# VESC_POWER_75100_SCH.net
KiCad netlist of a schematic drawn in Altium Designer
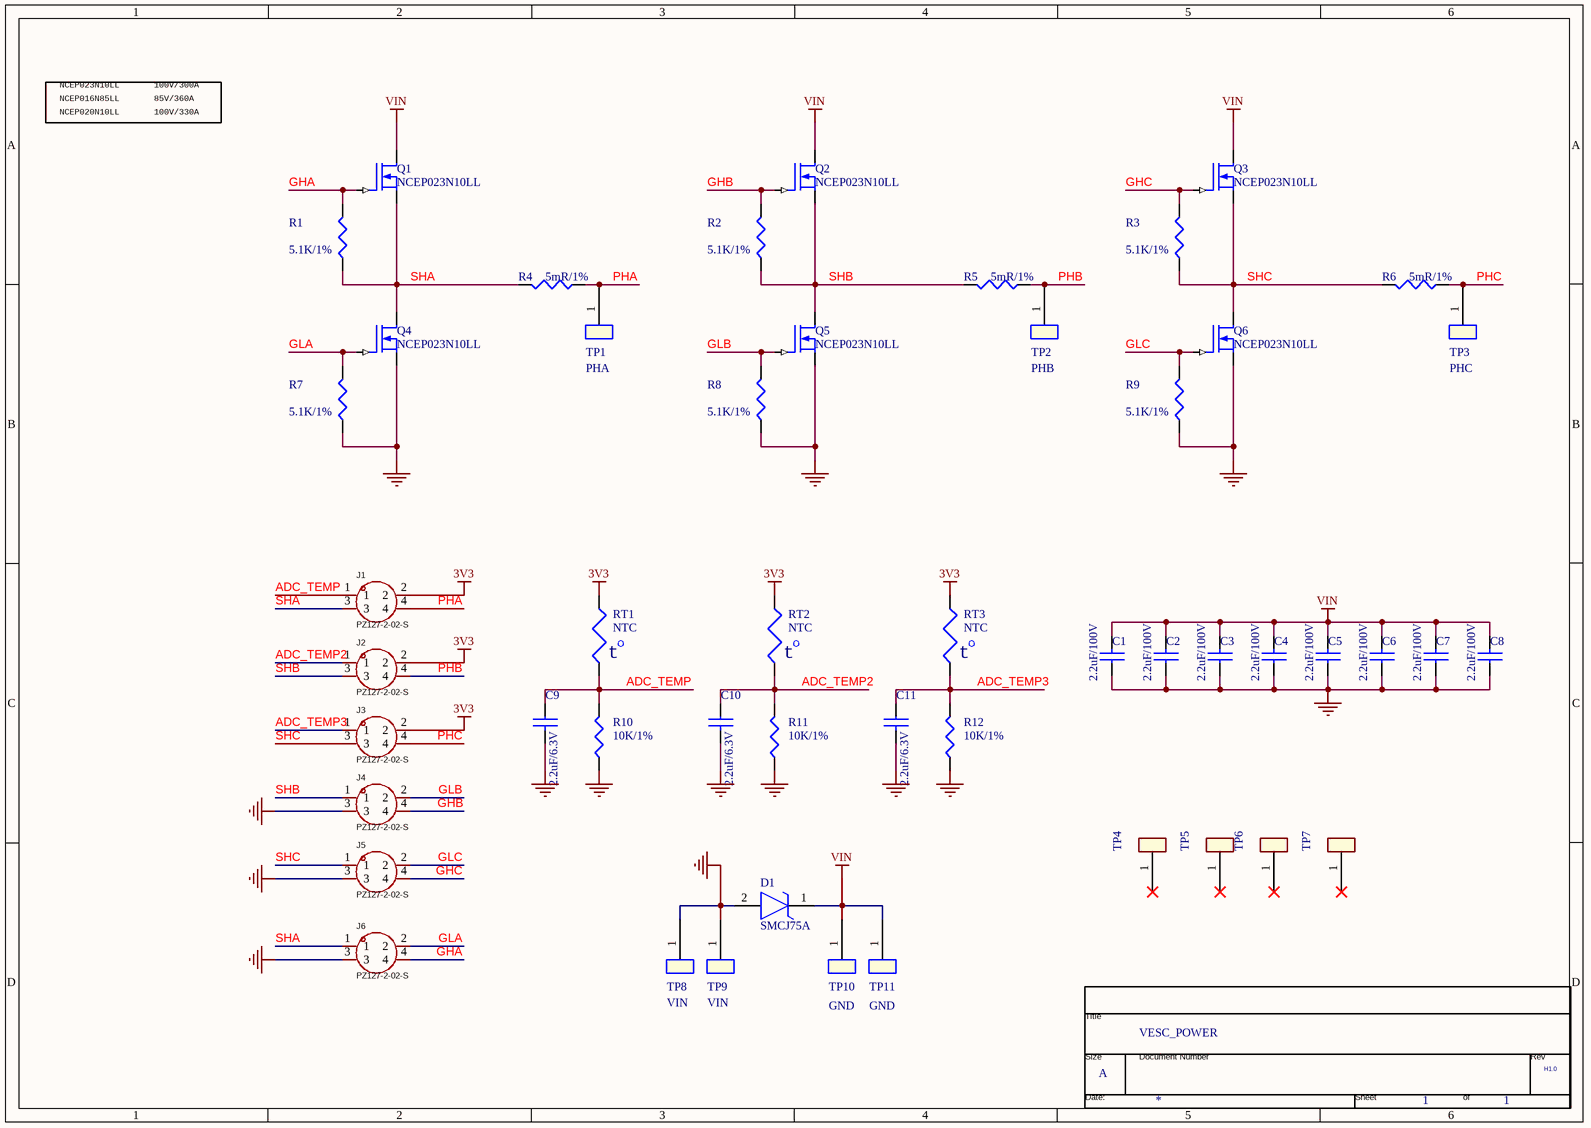
[diagram p0: VESC_POWER_75100_SCH.SchDoc]

(export (version "E")
  (design (tool "Eeschema 10.0.6"))
  (components
    (comp (ref "*")
      (value "TitleBlock0")
      (fields
        (field (name "REVCODE") "H1.0")
        (field (name "TITLE") "VESC_POWER")
        (field (name "PAGE SIZE") "A")
        (field (name "PAGE NUMBER") "1")
        (field (name "PAGE COUNT") "1")
      )
      (libsource (lib "*") (part "TitleBlock0"))
    )
    (comp (ref "C1") (value "2.2uF/100V") (footprint "CAPC3225X230N") (libsource (lib "*") (part "CAP NP")))
    (comp (ref "C2") (value "2.2uF/100V") (footprint "CAPC3225X230N") (libsource (lib "*") (part "CAP NP")))
    (comp (ref "C3") (value "2.2uF/100V") (footprint "CAPC3225X230N") (libsource (lib "*") (part "CAP NP")))
    (comp (ref "C4") (value "2.2uF/100V") (footprint "CAPC3225X230N") (libsource (lib "*") (part "CAP NP")))
    (comp (ref "C5") (value "2.2uF/100V") (footprint "CAPC3225X230N") (libsource (lib "*") (part "CAP NP")))
    (comp (ref "C6") (value "2.2uF/100V") (footprint "CAPC3225X230N") (libsource (lib "*") (part "CAP NP")))
    (comp (ref "C7") (value "2.2uF/100V") (footprint "CAPC3225X230N") (libsource (lib "*") (part "CAP NP")))
    (comp (ref "C8") (value "2.2uF/100V") (footprint "CAPC3225X230N") (libsource (lib "*") (part "CAP NP")))
    (comp (ref "C9") (value "2.2uF/6.3V") (footprint "C0603") (libsource (lib "*") (part "CAP NP")))
    (comp (ref "C10") (value "2.2uF/6.3V") (footprint "C0603") (libsource (lib "*") (part "CAP NP")))
    (comp (ref "C11") (value "2.2uF/6.3V") (footprint "C0603") (libsource (lib "*") (part "CAP NP")))
    (comp (ref "D1")
      (value "SMCJ75A")
      (footprint "DIOM7959X262N")
      (description "TVS Diode (Uni-directional)")
      (fields (field (name "MOUSER PART NUMBER") "652-SMCJ75A"))
      (libsource (lib "VESC_POWER_Library") (part "SMCJ75A"))
    )
    (comp (ref "J1")
      (value "PZ127-2-02-S")
      (footprint "HDR-SMD_4P-P1.27-V-M-R2-C2-LS5.3")
      (fields (field (name "MANUFACTURER") "HCTL(华灿天禄)"))
      (libsource (lib "VESC_POWER_Library") (part "PZ127-2-02-S"))
    )
    (comp (ref "J2")
      (value "PZ127-2-02-S")
      (footprint "HDR-SMD_4P-P1.27-V-M-R2-C2-LS5.3")
      (fields (field (name "MANUFACTURER") "HCTL(华灿天禄)"))
      (libsource (lib "VESC_POWER_Library") (part "PZ127-2-02-S"))
    )
    (comp (ref "J3")
      (value "PZ127-2-02-S")
      (footprint "HDR-SMD_4P-P1.27-V-M-R2-C2-LS5.3")
      (fields (field (name "MANUFACTURER") "HCTL(华灿天禄)"))
      (libsource (lib "VESC_POWER_Library") (part "PZ127-2-02-S"))
    )
    (comp (ref "J4")
      (value "PZ127-2-02-S")
      (footprint "HDR-SMD_4P-P1.27-V-M-R2-C2-LS5.3")
      (fields (field (name "MANUFACTURER") "HCTL(华灿天禄)"))
      (libsource (lib "VESC_POWER_Library") (part "PZ127-2-02-S"))
    )
    (comp (ref "J5")
      (value "PZ127-2-02-S")
      (footprint "HDR-SMD_4P-P1.27-V-M-R2-C2-LS5.3")
      (fields (field (name "MANUFACTURER") "HCTL(华灿天禄)"))
      (libsource (lib "VESC_POWER_Library") (part "PZ127-2-02-S"))
    )
    (comp (ref "J6")
      (value "PZ127-2-02-S")
      (footprint "HDR-SMD_4P-P1.27-V-M-R2-C2-LS5.3")
      (fields (field (name "MANUFACTURER") "HCTL(华灿天禄)"))
      (libsource (lib "VESC_POWER_Library") (part "PZ127-2-02-S"))
    )
    (comp (ref "Q1") (value "NCEP023N10LL") (footprint "TOLL") (libsource (lib "*") (part "MOSFET N")))
    (comp (ref "Q2") (value "NCEP023N10LL") (footprint "TOLL") (libsource (lib "*") (part "MOSFET N")))
    (comp (ref "Q3") (value "NCEP023N10LL") (footprint "TOLL") (libsource (lib "*") (part "MOSFET N")))
    (comp (ref "Q4") (value "NCEP023N10LL") (footprint "TOLL") (libsource (lib "*") (part "MOSFET N")))
    (comp (ref "Q5") (value "NCEP023N10LL") (footprint "TOLL") (libsource (lib "*") (part "MOSFET N")))
    (comp (ref "Q6") (value "NCEP023N10LL") (footprint "TOLL") (libsource (lib "*") (part "MOSFET N")))
    (comp (ref "R1") (value "5.1K/1%") (footprint "R0603") (libsource (lib "*") (part "RESISTOR")))
    (comp (ref "R2") (value "5.1K/1%") (footprint "R0603") (libsource (lib "*") (part "RESISTOR")))
    (comp (ref "R3") (value "5.1K/1%") (footprint "R0603") (libsource (lib "*") (part "RESISTOR")))
    (comp (ref "R4") (value "5mR/1%") (footprint "R2512") (libsource (lib "*") (part "RESISTOR")))
    (comp (ref "R5") (value "5mR/1%") (footprint "R2512") (libsource (lib "*") (part "RESISTOR")))
    (comp (ref "R6") (value "5mR/1%") (footprint "R2512") (libsource (lib "*") (part "RESISTOR")))
    (comp (ref "R7") (value "5.1K/1%") (footprint "R0603") (libsource (lib "*") (part "RESISTOR")))
    (comp (ref "R8") (value "5.1K/1%") (footprint "R0603") (libsource (lib "*") (part "RESISTOR")))
    (comp (ref "R9") (value "5.1K/1%") (footprint "R0603") (libsource (lib "*") (part "RESISTOR")))
    (comp (ref "R10") (value "10K/1%") (footprint "R0603") (libsource (lib "*") (part "RESISTOR")))
    (comp (ref "R11") (value "10K/1%") (footprint "R0603") (libsource (lib "*") (part "RESISTOR")))
    (comp (ref "R12") (value "10K/1%") (footprint "R0603") (libsource (lib "*") (part "RESISTOR")))
    (comp (ref "RT1") (value "NTC") (footprint "R0603") (libsource (lib "*") (part "NTC")))
    (comp (ref "RT2") (value "NTC") (footprint "R0603") (libsource (lib "*") (part "NTC")))
    (comp (ref "RT3") (value "NTC") (footprint "R0603") (libsource (lib "*") (part "NTC")))
    (comp (ref "TP1") (value "PHA") (footprint "TP_8x8") (libsource (lib "*") (part "TEST POINT")))
    (comp (ref "TP2") (value "PHB") (footprint "TP_8x8") (libsource (lib "*") (part "TEST POINT")))
    (comp (ref "TP3") (value "PHC") (footprint "TP_8x8") (libsource (lib "*") (part "TEST POINT")))
    (comp (ref "TP4")
      (value "TEST POINT")
      (footprint "HOLE-3.2MM_M")
      (libsource (lib "VESC_POWER_Library") (part "TEST POINT"))
    )
    (comp (ref "TP5")
      (value "TEST POINT")
      (footprint "HOLE-3.2MM_M")
      (libsource (lib "VESC_POWER_Library") (part "TEST POINT"))
    )
    (comp (ref "TP6")
      (value "TEST POINT")
      (footprint "HOLE-3.2MM_M")
      (libsource (lib "VESC_POWER_Library") (part "TEST POINT"))
    )
    (comp (ref "TP7")
      (value "TEST POINT")
      (footprint "HOLE-3.2MM_M")
      (libsource (lib "VESC_POWER_Library") (part "TEST POINT"))
    )
    (comp (ref "TP8") (value "VIN") (footprint "TP_6x6") (libsource (lib "*") (part "TEST POINT")))
    (comp (ref "TP9") (value "VIN") (footprint "TP_8x8") (libsource (lib "*") (part "TEST POINT")))
    (comp (ref "TP10") (value "GND") (footprint "TP_8x8") (libsource (lib "*") (part "TEST POINT")))
    (comp (ref "TP11") (value "GND") (footprint "TP_6x6") (libsource (lib "*") (part "TEST POINT")))
  )
  (nets
    (net (code "1") (name "/ADC_TEMP") (class "Default")
      (node (ref "C9") (pin "1") (pinfunction "1_1") (pintype "passive"))
      (node (ref "J1") (pin "1") (pinfunction "1_1") (pintype "passive"))
      (node (ref "R10") (pin "2") (pinfunction "2_2") (pintype "passive"))
      (node (ref "RT1") (pin "2") (pinfunction "2_2") (pintype "passive"))
    )
    (net (code "2") (name "/ADC_TEMP2") (class "Default")
      (node (ref "C10") (pin "1") (pinfunction "1_1") (pintype "passive"))
      (node (ref "J2") (pin "1") (pinfunction "1_1") (pintype "passive"))
      (node (ref "R11") (pin "2") (pinfunction "2_2") (pintype "passive"))
      (node (ref "RT2") (pin "2") (pinfunction "2_2") (pintype "passive"))
    )
    (net (code "3") (name "/ADC_TEMP3") (class "Default")
      (node (ref "C11") (pin "1") (pinfunction "1_1") (pintype "passive"))
      (node (ref "J3") (pin "1") (pinfunction "1_1") (pintype "passive"))
      (node (ref "R12") (pin "2") (pinfunction "2_2") (pintype "passive"))
      (node (ref "RT3") (pin "2") (pinfunction "2_2") (pintype "passive"))
    )
    (net (code "4") (name "/GHA") (class "Default")
      (node (ref "J6") (pin "4") (pinfunction "4_4") (pintype "passive"))
      (node (ref "Q1") (pin "1") (pinfunction "GATE_1") (pintype "input"))
      (node (ref "R1") (pin "2") (pinfunction "2_2") (pintype "passive"))
    )
    (net (code "5") (name "/GHB") (class "Default")
      (node (ref "J4") (pin "4") (pinfunction "4_4") (pintype "passive"))
      (node (ref "Q2") (pin "1") (pinfunction "GATE_1") (pintype "input"))
      (node (ref "R2") (pin "2") (pinfunction "2_2") (pintype "passive"))
    )
    (net (code "6") (name "/GHC") (class "Default")
      (node (ref "J5") (pin "4") (pinfunction "4_4") (pintype "passive"))
      (node (ref "Q3") (pin "1") (pinfunction "GATE_1") (pintype "input"))
      (node (ref "R3") (pin "2") (pinfunction "2_2") (pintype "passive"))
    )
    (net (code "7") (name "/GLA") (class "Default")
      (node (ref "J6") (pin "2") (pinfunction "2_2") (pintype "passive"))
      (node (ref "Q4") (pin "1") (pinfunction "GATE_1") (pintype "input"))
      (node (ref "R7") (pin "2") (pinfunction "2_2") (pintype "passive"))
    )
    (net (code "8") (name "/GLB") (class "Default")
      (node (ref "J4") (pin "2") (pinfunction "2_2") (pintype "passive"))
      (node (ref "Q5") (pin "1") (pinfunction "GATE_1") (pintype "input"))
      (node (ref "R8") (pin "2") (pinfunction "2_2") (pintype "passive"))
    )
    (net (code "9") (name "/GLC") (class "Default")
      (node (ref "J5") (pin "2") (pinfunction "2_2") (pintype "passive"))
      (node (ref "Q6") (pin "1") (pinfunction "GATE_1") (pintype "input"))
      (node (ref "R9") (pin "2") (pinfunction "2_2") (pintype "passive"))
    )
    (net (code "10") (name "/PHA") (class "Default")
      (node (ref "J1") (pin "4") (pinfunction "4_4") (pintype "passive"))
      (node (ref "R4") (pin "1") (pinfunction "1_1") (pintype "passive"))
      (node (ref "TP1") (pin "1") (pinfunction "1_1") (pintype "passive"))
    )
    (net (code "11") (name "/PHB") (class "Default")
      (node (ref "J2") (pin "4") (pinfunction "4_4") (pintype "passive"))
      (node (ref "R5") (pin "1") (pinfunction "1_1") (pintype "passive"))
      (node (ref "TP2") (pin "1") (pinfunction "1_1") (pintype "passive"))
    )
    (net (code "12") (name "/PHC") (class "Default")
      (node (ref "J3") (pin "4") (pinfunction "4_4") (pintype "passive"))
      (node (ref "R6") (pin "1") (pinfunction "1_1") (pintype "passive"))
      (node (ref "TP3") (pin "1") (pinfunction "1_1") (pintype "passive"))
    )
    (net (code "13") (name "/SHA") (class "Default")
      (node (ref "J1") (pin "3") (pinfunction "3_3") (pintype "passive"))
      (node (ref "J6") (pin "1") (pinfunction "1_1") (pintype "passive"))
      (node (ref "Q1") (pin "3") (pinfunction "SOURCE_3") (pintype "passive"))
      (node (ref "Q4") (pin "2") (pinfunction "DRAIN_2") (pintype "passive"))
      (node (ref "R1") (pin "1") (pinfunction "1_1") (pintype "passive"))
      (node (ref "R4") (pin "2") (pinfunction "2_2") (pintype "passive"))
    )
    (net (code "14") (name "/SHB") (class "Default")
      (node (ref "J2") (pin "3") (pinfunction "3_3") (pintype "passive"))
      (node (ref "J4") (pin "1") (pinfunction "1_1") (pintype "passive"))
      (node (ref "Q2") (pin "3") (pinfunction "SOURCE_3") (pintype "passive"))
      (node (ref "Q5") (pin "2") (pinfunction "DRAIN_2") (pintype "passive"))
      (node (ref "R2") (pin "1") (pinfunction "1_1") (pintype "passive"))
      (node (ref "R5") (pin "2") (pinfunction "2_2") (pintype "passive"))
    )
    (net (code "15") (name "/SHC") (class "Default")
      (node (ref "J3") (pin "3") (pinfunction "3_3") (pintype "passive"))
      (node (ref "J5") (pin "1") (pinfunction "1_1") (pintype "passive"))
      (node (ref "Q3") (pin "3") (pinfunction "SOURCE_3") (pintype "passive"))
      (node (ref "Q6") (pin "2") (pinfunction "DRAIN_2") (pintype "passive"))
      (node (ref "R3") (pin "1") (pinfunction "1_1") (pintype "passive"))
      (node (ref "R6") (pin "2") (pinfunction "2_2") (pintype "passive"))
    )
    (net (code "16") (name "3V3") (class "Default")
      (node (ref "J1") (pin "2") (pinfunction "2_2") (pintype "passive"))
      (node (ref "J2") (pin "2") (pinfunction "2_2") (pintype "passive"))
      (node (ref "J3") (pin "2") (pinfunction "2_2") (pintype "passive"))
      (node (ref "RT1") (pin "1") (pinfunction "1_1") (pintype "passive"))
      (node (ref "RT2") (pin "1") (pinfunction "1_1") (pintype "passive"))
      (node (ref "RT3") (pin "1") (pinfunction "1_1") (pintype "passive"))
    )
    (net (code "17") (name "GND") (class "Default")
      (node (ref "C1") (pin "1") (pinfunction "1_1") (pintype "passive"))
      (node (ref "C10") (pin "2") (pinfunction "2_2") (pintype "passive"))
      (node (ref "C11") (pin "2") (pinfunction "2_2") (pintype "passive"))
      (node (ref "C2") (pin "1") (pinfunction "1_1") (pintype "passive"))
      (node (ref "C3") (pin "1") (pinfunction "1_1") (pintype "passive"))
      (node (ref "C4") (pin "1") (pinfunction "1_1") (pintype "passive"))
      (node (ref "C5") (pin "1") (pinfunction "1_1") (pintype "passive"))
      (node (ref "C6") (pin "1") (pinfunction "1_1") (pintype "passive"))
      (node (ref "C7") (pin "1") (pinfunction "1_1") (pintype "passive"))
      (node (ref "C8") (pin "1") (pinfunction "1_1") (pintype "passive"))
      (node (ref "C9") (pin "2") (pinfunction "2_2") (pintype "passive"))
      (node (ref "D1") (pin "2") (pinfunction "A_2") (pintype "passive"))
      (node (ref "J4") (pin "3") (pinfunction "3_3") (pintype "passive"))
      (node (ref "J5") (pin "3") (pinfunction "3_3") (pintype "passive"))
      (node (ref "J6") (pin "3") (pinfunction "3_3") (pintype "passive"))
      (node (ref "Q4") (pin "3") (pinfunction "SOURCE_3") (pintype "passive"))
      (node (ref "Q5") (pin "3") (pinfunction "SOURCE_3") (pintype "passive"))
      (node (ref "Q6") (pin "3") (pinfunction "SOURCE_3") (pintype "passive"))
      (node (ref "R10") (pin "1") (pinfunction "1_1") (pintype "passive"))
      (node (ref "R11") (pin "1") (pinfunction "1_1") (pintype "passive"))
      (node (ref "R12") (pin "1") (pinfunction "1_1") (pintype "passive"))
      (node (ref "R7") (pin "1") (pinfunction "1_1") (pintype "passive"))
      (node (ref "R8") (pin "1") (pinfunction "1_1") (pintype "passive"))
      (node (ref "R9") (pin "1") (pinfunction "1_1") (pintype "passive"))
      (node (ref "TP8") (pin "1") (pinfunction "1_1") (pintype "passive"))
      (node (ref "TP9") (pin "1") (pinfunction "1_1") (pintype "passive"))
    )
    (net (code "18") (name "VIN") (class "Default")
      (node (ref "C1") (pin "2") (pinfunction "2_2") (pintype "passive"))
      (node (ref "C2") (pin "2") (pinfunction "2_2") (pintype "passive"))
      (node (ref "C3") (pin "2") (pinfunction "2_2") (pintype "passive"))
      (node (ref "C4") (pin "2") (pinfunction "2_2") (pintype "passive"))
      (node (ref "C5") (pin "2") (pinfunction "2_2") (pintype "passive"))
      (node (ref "C6") (pin "2") (pinfunction "2_2") (pintype "passive"))
      (node (ref "C7") (pin "2") (pinfunction "2_2") (pintype "passive"))
      (node (ref "C8") (pin "2") (pinfunction "2_2") (pintype "passive"))
      (node (ref "D1") (pin "1") (pinfunction "K_1") (pintype "passive"))
      (node (ref "Q1") (pin "2") (pinfunction "DRAIN_2") (pintype "passive"))
      (node (ref "Q2") (pin "2") (pinfunction "DRAIN_2") (pintype "passive"))
      (node (ref "Q3") (pin "2") (pinfunction "DRAIN_2") (pintype "passive"))
      (node (ref "TP10") (pin "1") (pinfunction "1_1") (pintype "passive"))
      (node (ref "TP11") (pin "1") (pinfunction "1_1") (pintype "passive"))
    )
    (net (code "19") (name "unconnected-(TP4-Pad1)") (class "Default")
      (node (ref "TP4") (pin "1") (pinfunction "1_1") (pintype "passive+no_connect"))
    )
    (net (code "20") (name "unconnected-(TP5-Pad1)") (class "Default")
      (node (ref "TP5") (pin "1") (pinfunction "1_1") (pintype "passive+no_connect"))
    )
    (net (code "21") (name "unconnected-(TP6-Pad1)") (class "Default")
      (node (ref "TP6") (pin "1") (pinfunction "1_1") (pintype "passive+no_connect"))
    )
    (net (code "22") (name "unconnected-(TP7-Pad1)") (class "Default")
      (node (ref "TP7") (pin "1") (pinfunction "1_1") (pintype "passive+no_connect"))
    )
  )
)
